# Ffrydiau_core1_1.net
KiCad netlist of a schematic drawn in EAGLE
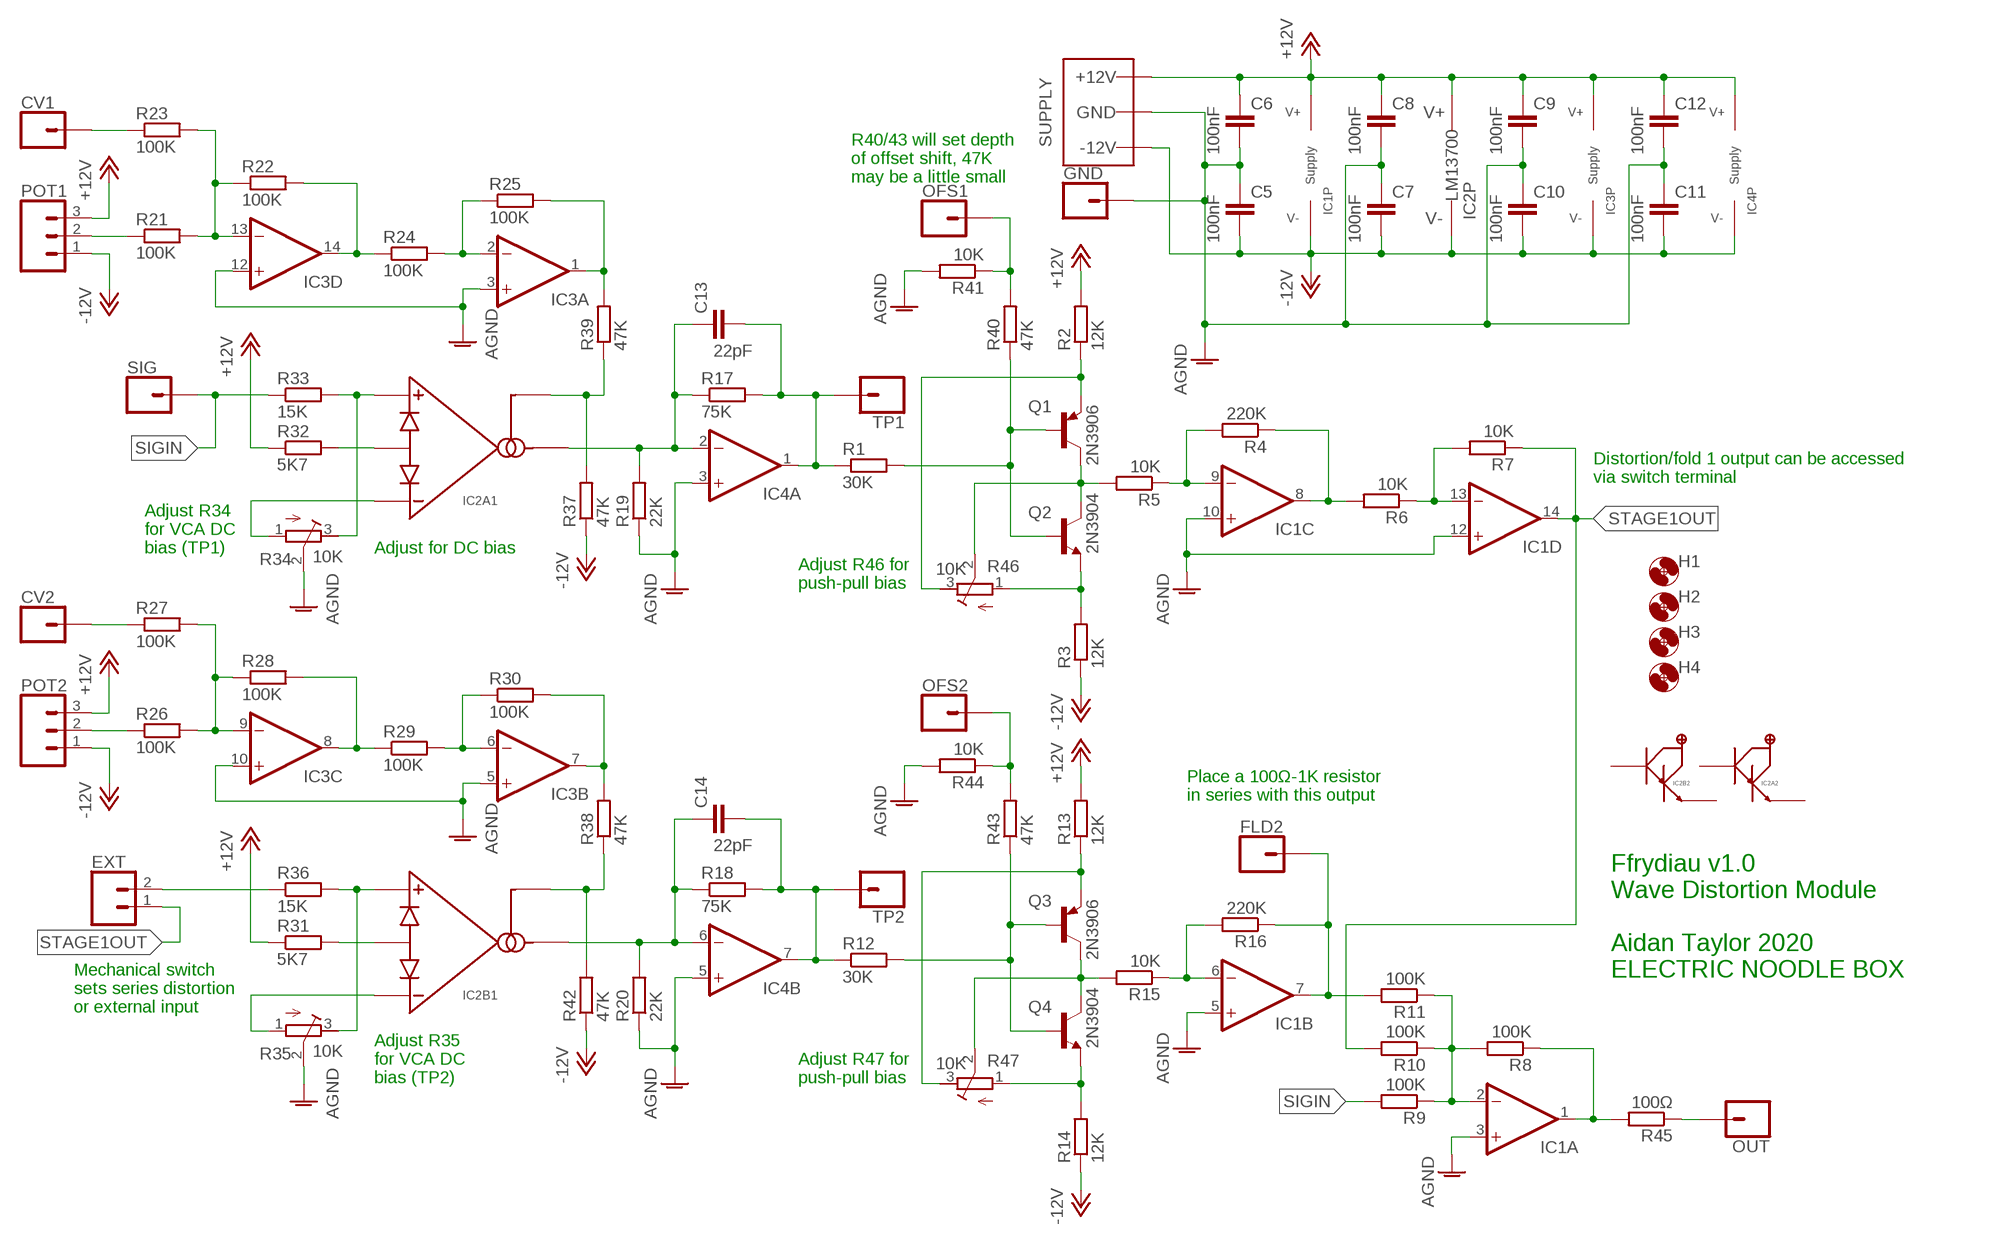
[diagram p0: schematic, sheet 1]

(export (version "E")
  (design (tool "Eeschema 10.0.6"))
  (components
    (comp (ref "C5")
      (value "100nF")
      (footprint "eagle-import:C050-025X075")
      (libsource (lib "eagle-import") (part "C-EU050-025X075"))
    )
    (comp (ref "C6")
      (value "100nF")
      (footprint "eagle-import:C050-025X075")
      (libsource (lib "eagle-import") (part "C-EU050-025X075"))
    )
    (comp (ref "C7")
      (value "100nF")
      (footprint "eagle-import:C050-025X075")
      (libsource (lib "eagle-import") (part "C-EU050-025X075"))
    )
    (comp (ref "C8")
      (value "100nF")
      (footprint "eagle-import:C050-025X075")
      (libsource (lib "eagle-import") (part "C-EU050-025X075"))
    )
    (comp (ref "C9")
      (value "100nF")
      (footprint "eagle-import:C050-025X075")
      (libsource (lib "eagle-import") (part "C-EU050-025X075"))
    )
    (comp (ref "C10")
      (value "100nF")
      (footprint "eagle-import:C050-025X075")
      (libsource (lib "eagle-import") (part "C-EU050-025X075"))
    )
    (comp (ref "C11")
      (value "100nF")
      (footprint "eagle-import:C050-025X075")
      (libsource (lib "eagle-import") (part "C-EU050-025X075"))
    )
    (comp (ref "C12")
      (value "100nF")
      (footprint "eagle-import:C050-025X075")
      (libsource (lib "eagle-import") (part "C-EU050-025X075"))
    )
    (comp (ref "C13")
      (value "22pF")
      (footprint "eagle-import:C050-025X075")
      (libsource (lib "eagle-import") (part "C-EU050-025X075"))
    )
    (comp (ref "C14")
      (value "22pF")
      (footprint "eagle-import:C050-025X075")
      (libsource (lib "eagle-import") (part "C-EU050-025X075"))
    )
    (comp (ref "CV1")
      (value "1XWIREPAD")
      (footprint "eagle-import:1X01")
      (libsource (lib "eagle-import") (part "1XWIREPAD"))
    )
    (comp (ref "CV2")
      (value "1XWIREPAD")
      (footprint "eagle-import:1X01")
      (libsource (lib "eagle-import") (part "1XWIREPAD"))
    )
    (comp (ref "EXT")
      (value "2XWIREPAD")
      (footprint "eagle-import:1X02")
      (libsource (lib "eagle-import") (part "2XWIREPAD"))
    )
    (comp (ref "FLD2")
      (value "1XWIREPAD")
      (footprint "eagle-import:1X01")
      (libsource (lib "eagle-import") (part "1XWIREPAD"))
    )
    (comp (ref "GND")
      (value "1XWIREPAD")
      (footprint "eagle-import:1X01")
      (libsource (lib "eagle-import") (part "1XWIREPAD"))
    )
    (comp (ref "H1")
      (value "MOUNT-HOLE3.2")
      (footprint "eagle-import:3,2")
      (libsource (lib "eagle-import") (part "MOUNT-HOLE3.2"))
    )
    (comp (ref "H2")
      (value "MOUNT-HOLE3.2")
      (footprint "eagle-import:3,2")
      (libsource (lib "eagle-import") (part "MOUNT-HOLE3.2"))
    )
    (comp (ref "H3")
      (value "MOUNT-HOLE3.2")
      (footprint "eagle-import:3,2")
      (libsource (lib "eagle-import") (part "MOUNT-HOLE3.2"))
    )
    (comp (ref "H4")
      (value "MOUNT-HOLE3.2")
      (footprint "eagle-import:3,2")
      (libsource (lib "eagle-import") (part "MOUNT-HOLE3.2"))
    )
    (comp (ref "IC1")
      (value "TL0X4DIL")
      (footprint "eagle-import:DIL14")
      (libsource (lib "eagle-import") (part "TL0X4DIL"))
    )
    (comp (ref "IC2")
      (value "LM13700DIL")
      (footprint "eagle-import:DIL16")
      (libsource (lib "eagle-import") (part "LM13700DIL"))
    )
    (comp (ref "IC3")
      (value "TL0X4DIL")
      (footprint "eagle-import:DIL14")
      (libsource (lib "eagle-import") (part "TL0X4DIL"))
    )
    (comp (ref "IC4")
      (value "TL0X2DIL")
      (footprint "eagle-import:DIL08")
      (libsource (lib "eagle-import") (part "TL0X2DIL"))
    )
    (comp (ref "OFS1")
      (value "1XWIREPAD")
      (footprint "eagle-import:1X01")
      (libsource (lib "eagle-import") (part "1XWIREPAD"))
    )
    (comp (ref "OFS2")
      (value "1XWIREPAD")
      (footprint "eagle-import:1X01")
      (libsource (lib "eagle-import") (part "1XWIREPAD"))
    )
    (comp (ref "OUT")
      (value "1XWIREPAD")
      (footprint "eagle-import:1X01")
      (libsource (lib "eagle-import") (part "1XWIREPAD"))
    )
    (comp (ref "POT1")
      (value "3XWIREPAD")
      (footprint "eagle-import:1X03")
      (libsource (lib "eagle-import") (part "3XWIREPAD"))
    )
    (comp (ref "POT2")
      (value "3XWIREPAD")
      (footprint "eagle-import:1X03")
      (libsource (lib "eagle-import") (part "3XWIREPAD"))
    )
    (comp (ref "Q1")
      (value "2N3906")
      (footprint "eagle-import:TO92")
      (libsource (lib "eagle-import") (part "2N3906"))
    )
    (comp (ref "Q2")
      (value "2N3904")
      (footprint "eagle-import:TO92")
      (libsource (lib "eagle-import") (part "2N3904"))
    )
    (comp (ref "Q3")
      (value "2N3906")
      (footprint "eagle-import:TO92")
      (libsource (lib "eagle-import") (part "2N3906"))
    )
    (comp (ref "Q4")
      (value "2N3904")
      (footprint "eagle-import:TO92")
      (libsource (lib "eagle-import") (part "2N3904"))
    )
    (comp (ref "R1")
      (value "30K")
      (footprint "eagle-import:0207_7")
      (libsource (lib "eagle-import") (part "R-EU_0207/7"))
    )
    (comp (ref "R2")
      (value "12K")
      (footprint "eagle-import:0207_7")
      (libsource (lib "eagle-import") (part "R-EU_0207/7"))
    )
    (comp (ref "R3")
      (value "12K")
      (footprint "eagle-import:0207_7")
      (libsource (lib "eagle-import") (part "R-EU_0207/7"))
    )
    (comp (ref "R4")
      (value "220K")
      (footprint "eagle-import:0207_7")
      (libsource (lib "eagle-import") (part "R-EU_0207/7"))
    )
    (comp (ref "R5")
      (value "10K")
      (footprint "eagle-import:0207_7")
      (libsource (lib "eagle-import") (part "R-EU_0207/7"))
    )
    (comp (ref "R6")
      (value "10K")
      (footprint "eagle-import:0207_7")
      (libsource (lib "eagle-import") (part "R-EU_0207/7"))
    )
    (comp (ref "R7")
      (value "10K")
      (footprint "eagle-import:0207_7")
      (libsource (lib "eagle-import") (part "R-EU_0207/7"))
    )
    (comp (ref "R8")
      (value "100K")
      (footprint "eagle-import:0207_7")
      (libsource (lib "eagle-import") (part "R-EU_0207/7"))
    )
    (comp (ref "R9")
      (value "100K")
      (footprint "eagle-import:0207_7")
      (libsource (lib "eagle-import") (part "R-EU_0207/7"))
    )
    (comp (ref "R10")
      (value "100K")
      (footprint "eagle-import:0207_7")
      (libsource (lib "eagle-import") (part "R-EU_0207/7"))
    )
    (comp (ref "R11")
      (value "100K")
      (footprint "eagle-import:0207_7")
      (libsource (lib "eagle-import") (part "R-EU_0207/7"))
    )
    (comp (ref "R12")
      (value "30K")
      (footprint "eagle-import:0207_7")
      (libsource (lib "eagle-import") (part "R-EU_0207/7"))
    )
    (comp (ref "R13")
      (value "12K")
      (footprint "eagle-import:0207_7")
      (libsource (lib "eagle-import") (part "R-EU_0207/7"))
    )
    (comp (ref "R14")
      (value "12K")
      (footprint "eagle-import:0207_7")
      (libsource (lib "eagle-import") (part "R-EU_0207/7"))
    )
    (comp (ref "R15")
      (value "10K")
      (footprint "eagle-import:0207_7")
      (libsource (lib "eagle-import") (part "R-EU_0207/7"))
    )
    (comp (ref "R16")
      (value "220K")
      (footprint "eagle-import:0207_7")
      (libsource (lib "eagle-import") (part "R-EU_0207/7"))
    )
    (comp (ref "R17")
      (value "75K")
      (footprint "eagle-import:0207_7")
      (libsource (lib "eagle-import") (part "R-EU_0207/7"))
    )
    (comp (ref "R18")
      (value "75K")
      (footprint "eagle-import:0207_7")
      (libsource (lib "eagle-import") (part "R-EU_0207/7"))
    )
    (comp (ref "R19")
      (value "22K")
      (footprint "eagle-import:0207_7")
      (libsource (lib "eagle-import") (part "R-EU_0207/7"))
    )
    (comp (ref "R20")
      (value "22K")
      (footprint "eagle-import:0207_7")
      (libsource (lib "eagle-import") (part "R-EU_0207/7"))
    )
    (comp (ref "R21")
      (value "100K")
      (footprint "eagle-import:0207_7")
      (libsource (lib "eagle-import") (part "R-EU_0207/7"))
    )
    (comp (ref "R22")
      (value "100K")
      (footprint "eagle-import:0207_7")
      (libsource (lib "eagle-import") (part "R-EU_0207/7"))
    )
    (comp (ref "R23")
      (value "100K")
      (footprint "eagle-import:0207_7")
      (libsource (lib "eagle-import") (part "R-EU_0207/7"))
    )
    (comp (ref "R24")
      (value "100K")
      (footprint "eagle-import:0207_7")
      (libsource (lib "eagle-import") (part "R-EU_0207/7"))
    )
    (comp (ref "R25")
      (value "100K")
      (footprint "eagle-import:0207_7")
      (libsource (lib "eagle-import") (part "R-EU_0207/7"))
    )
    (comp (ref "R26")
      (value "100K")
      (footprint "eagle-import:0207_7")
      (libsource (lib "eagle-import") (part "R-EU_0207/7"))
    )
    (comp (ref "R27")
      (value "100K")
      (footprint "eagle-import:0207_7")
      (libsource (lib "eagle-import") (part "R-EU_0207/7"))
    )
    (comp (ref "R28")
      (value "100K")
      (footprint "eagle-import:0207_7")
      (libsource (lib "eagle-import") (part "R-EU_0207/7"))
    )
    (comp (ref "R29")
      (value "100K")
      (footprint "eagle-import:0207_7")
      (libsource (lib "eagle-import") (part "R-EU_0207/7"))
    )
    (comp (ref "R30")
      (value "100K")
      (footprint "eagle-import:0207_7")
      (libsource (lib "eagle-import") (part "R-EU_0207/7"))
    )
    (comp (ref "R31")
      (value "5K7")
      (footprint "eagle-import:0207_7")
      (libsource (lib "eagle-import") (part "R-EU_0207/7"))
    )
    (comp (ref "R32")
      (value "5K7")
      (footprint "eagle-import:0207_7")
      (libsource (lib "eagle-import") (part "R-EU_0207/7"))
    )
    (comp (ref "R33")
      (value "15K")
      (footprint "eagle-import:0207_7")
      (libsource (lib "eagle-import") (part "R-EU_0207/7"))
    )
    (comp (ref "R34")
      (value "10K")
      (footprint "eagle-import:RTRIM3296W")
      (libsource (lib "eagle-import") (part "R-TRIMM3296W"))
    )
    (comp (ref "R35")
      (value "10K")
      (footprint "eagle-import:RTRIM3296W")
      (libsource (lib "eagle-import") (part "R-TRIMM3296W"))
    )
    (comp (ref "R36")
      (value "15K")
      (footprint "eagle-import:0207_7")
      (libsource (lib "eagle-import") (part "R-EU_0207/7"))
    )
    (comp (ref "R37")
      (value "47K")
      (footprint "eagle-import:0207_7")
      (libsource (lib "eagle-import") (part "R-EU_0207/7"))
    )
    (comp (ref "R38")
      (value "47K")
      (footprint "eagle-import:0207_7")
      (libsource (lib "eagle-import") (part "R-EU_0207/7"))
    )
    (comp (ref "R39")
      (value "47K")
      (footprint "eagle-import:0207_7")
      (libsource (lib "eagle-import") (part "R-EU_0207/7"))
    )
    (comp (ref "R40")
      (value "47K")
      (footprint "eagle-import:0207_7")
      (libsource (lib "eagle-import") (part "R-EU_0207/7"))
    )
    (comp (ref "R41")
      (value "10K")
      (footprint "eagle-import:0207_7")
      (libsource (lib "eagle-import") (part "R-EU_0207/7"))
    )
    (comp (ref "R42")
      (value "47K")
      (footprint "eagle-import:0207_7")
      (libsource (lib "eagle-import") (part "R-EU_0207/7"))
    )
    (comp (ref "R43")
      (value "47K")
      (footprint "eagle-import:0207_7")
      (libsource (lib "eagle-import") (part "R-EU_0207/7"))
    )
    (comp (ref "R44")
      (value "10K")
      (footprint "eagle-import:0207_7")
      (libsource (lib "eagle-import") (part "R-EU_0207/7"))
    )
    (comp (ref "R45")
      (value "100Ω")
      (footprint "eagle-import:0207_7")
      (libsource (lib "eagle-import") (part "R-EU_0207/7"))
    )
    (comp (ref "R46")
      (value "10K")
      (footprint "eagle-import:RTRIM3296W")
      (libsource (lib "eagle-import") (part "R-TRIMM3296W"))
    )
    (comp (ref "R47")
      (value "10K")
      (footprint "eagle-import:RTRIM3296W")
      (libsource (lib "eagle-import") (part "R-TRIMM3296W"))
    )
    (comp (ref "SIG")
      (value "1XWIREPAD")
      (footprint "eagle-import:1X01")
      (libsource (lib "eagle-import") (part "1XWIREPAD"))
    )
    (comp (ref "TP1")
      (value "1XWIREPAD")
      (footprint "eagle-import:1X01")
      (libsource (lib "eagle-import") (part "1XWIREPAD"))
    )
    (comp (ref "TP2")
      (value "1XWIREPAD")
      (footprint "eagle-import:1X01")
      (libsource (lib "eagle-import") (part "1XWIREPAD"))
    )
    (comp (ref "WP1")
      (value "COMBO_SUPPLY_HEADER")
      (footprint "eagle-import:COMBINED_POWER")
      (libsource (lib "eagle-import") (part "COMBO_SUPPLY_HEADER"))
    )
  )
  (nets
    (net (code "1") (name "+12V") (class "Default")
      (node (ref "C12") (pin "1") (pinfunction "1_1") (pintype "passive"))
      (node (ref "C6") (pin "1") (pinfunction "1_1") (pintype "passive"))
      (node (ref "C8") (pin "1") (pinfunction "1_1") (pintype "passive"))
      (node (ref "C9") (pin "1") (pinfunction "1_1") (pintype "passive"))
      (node (ref "IC1") (pin "4") (pinfunction "V+_4") (pintype "bidirectional"))
      (node (ref "IC2") (pin "11") (pinfunction "V+_11") (pintype "power_in"))
      (node (ref "IC3") (pin "4") (pinfunction "V+_4") (pintype "bidirectional"))
      (node (ref "IC4") (pin "8") (pinfunction "V+_8") (pintype "bidirectional"))
      (node (ref "POT1") (pin "3") (pinfunction "3_3") (pintype "passive"))
      (node (ref "POT2") (pin "3") (pinfunction "3_3") (pintype "passive"))
      (node (ref "R13") (pin "2") (pinfunction "2_2") (pintype "passive"))
      (node (ref "R2") (pin "2") (pinfunction "2_2") (pintype "passive"))
      (node (ref "R31") (pin "1") (pinfunction "1_1") (pintype "passive"))
      (node (ref "R32") (pin "1") (pinfunction "1_1") (pintype "passive"))
      (node (ref "WP1") (pin "V+1") (pinfunction "V++_V+1") (pintype "power_in"))
      (node (ref "WP1") (pin "V+2") (pinfunction "V++_V+2") (pintype "power_in"))
      (node (ref "WP1") (pin "V+3") (pinfunction "V++_V+3") (pintype "power_in"))
    )
    (net (code "2") (name "-12V") (class "Default")
      (node (ref "C10") (pin "2") (pinfunction "2_2") (pintype "passive"))
      (node (ref "C11") (pin "2") (pinfunction "2_2") (pintype "passive"))
      (node (ref "C5") (pin "2") (pinfunction "2_2") (pintype "passive"))
      (node (ref "C7") (pin "2") (pinfunction "2_2") (pintype "passive"))
      (node (ref "IC1") (pin "11") (pinfunction "V-_11") (pintype "bidirectional"))
      (node (ref "IC2") (pin "6") (pinfunction "V-_6") (pintype "power_in"))
      (node (ref "IC3") (pin "11") (pinfunction "V-_11") (pintype "bidirectional"))
      (node (ref "IC4") (pin "4") (pinfunction "V-_4") (pintype "bidirectional"))
      (node (ref "POT1") (pin "1") (pinfunction "1_1") (pintype "passive"))
      (node (ref "POT2") (pin "1") (pinfunction "1_1") (pintype "passive"))
      (node (ref "R14") (pin "1") (pinfunction "1_1") (pintype "passive"))
      (node (ref "R3") (pin "1") (pinfunction "1_1") (pintype "passive"))
      (node (ref "R37") (pin "1") (pinfunction "1_1") (pintype "passive"))
      (node (ref "R42") (pin "1") (pinfunction "1_1") (pintype "passive"))
      (node (ref "WP1") (pin "V-1") (pinfunction "V--_V-1") (pintype "power_in"))
      (node (ref "WP1") (pin "V-2") (pinfunction "V--_V-2") (pintype "power_in"))
      (node (ref "WP1") (pin "V-3") (pinfunction "V--_V-3") (pintype "power_in"))
    )
    (net (code "3") (name "AGND") (class "Default")
      (node (ref "C10") (pin "1") (pinfunction "1_1") (pintype "passive"))
      (node (ref "C11") (pin "1") (pinfunction "1_1") (pintype "passive"))
      (node (ref "C12") (pin "2") (pinfunction "2_2") (pintype "passive"))
      (node (ref "C5") (pin "1") (pinfunction "1_1") (pintype "passive"))
      (node (ref "C6") (pin "2") (pinfunction "2_2") (pintype "passive"))
      (node (ref "C7") (pin "1") (pinfunction "1_1") (pintype "passive"))
      (node (ref "C8") (pin "2") (pinfunction "2_2") (pintype "passive"))
      (node (ref "C9") (pin "2") (pinfunction "2_2") (pintype "passive"))
      (node (ref "GND") (pin "1") (pinfunction "1_1") (pintype "passive"))
      (node (ref "IC1") (pin "10") (pinfunction "+IN_10") (pintype "input"))
      (node (ref "IC1") (pin "12") (pinfunction "+IN_12") (pintype "input"))
      (node (ref "IC1") (pin "3") (pinfunction "+IN_3") (pintype "input"))
      (node (ref "IC1") (pin "5") (pinfunction "+IN_5") (pintype "input"))
      (node (ref "IC3") (pin "10") (pinfunction "+IN_10") (pintype "input"))
      (node (ref "IC3") (pin "12") (pinfunction "+IN_12") (pintype "input"))
      (node (ref "IC3") (pin "3") (pinfunction "+IN_3") (pintype "input"))
      (node (ref "IC3") (pin "5") (pinfunction "+IN_5") (pintype "input"))
      (node (ref "IC4") (pin "3") (pinfunction "+IN_3") (pintype "input"))
      (node (ref "IC4") (pin "5") (pinfunction "+IN_5") (pintype "input"))
      (node (ref "R19") (pin "1") (pinfunction "1_1") (pintype "passive"))
      (node (ref "R20") (pin "1") (pinfunction "1_1") (pintype "passive"))
      (node (ref "R34") (pin "2") (pinfunction "S_2") (pintype "passive"))
      (node (ref "R35") (pin "2") (pinfunction "S_2") (pintype "passive"))
      (node (ref "R41") (pin "2") (pinfunction "2_2") (pintype "passive"))
      (node (ref "R44") (pin "2") (pinfunction "2_2") (pintype "passive"))
      (node (ref "WP1") (pin "GND1") (pinfunction "AGND_GND1") (pintype "power_in"))
      (node (ref "WP1") (pin "GND2") (pinfunction "AGND_GND2") (pintype "power_in"))
      (node (ref "WP1") (pin "GND3") (pinfunction "AGND_GND3") (pintype "power_in"))
      (node (ref "WP1") (pin "GND4") (pinfunction "AGND_GND4") (pintype "power_in"))
      (node (ref "WP1") (pin "GND5") (pinfunction "AGND_GND5") (pintype "power_in"))
      (node (ref "WP1") (pin "GND6") (pinfunction "AGND_GND6") (pintype "power_in"))
      (node (ref "WP1") (pin "GND7") (pinfunction "AGND_GND7") (pintype "power_in"))
      (node (ref "WP1") (pin "GND8") (pinfunction "AGND_GND8") (pintype "power_in"))
    )
    (net (code "4") (name "Net-(CV1-Pad1)") (class "Default")
      (node (ref "CV1") (pin "1") (pinfunction "1_1") (pintype "passive"))
      (node (ref "R23") (pin "1") (pinfunction "1_1") (pintype "passive"))
    )
    (net (code "5") (name "Net-(CV2-Pad1)") (class "Default")
      (node (ref "CV2") (pin "1") (pinfunction "1_1") (pintype "passive"))
      (node (ref "R27") (pin "1") (pinfunction "1_1") (pintype "passive"))
    )
    (net (code "6") (name "Net-(EXT-Pad2)") (class "Default")
      (node (ref "EXT") (pin "2") (pinfunction "2_2") (pintype "passive"))
      (node (ref "R36") (pin "1") (pinfunction "1_1") (pintype "passive"))
    )
    (net (code "7") (name "Net-(IC1A--IN)") (class "Default")
      (node (ref "IC1") (pin "2") (pinfunction "-IN_2") (pintype "input"))
      (node (ref "R10") (pin "1") (pinfunction "1_1") (pintype "passive"))
      (node (ref "R11") (pin "1") (pinfunction "1_1") (pintype "passive"))
      (node (ref "R8") (pin "2") (pinfunction "2_2") (pintype "passive"))
      (node (ref "R9") (pin "1") (pinfunction "1_1") (pintype "passive"))
    )
    (net (code "8") (name "Net-(IC1A-OUT)") (class "Default")
      (node (ref "IC1") (pin "1") (pinfunction "OUT_1") (pintype "output"))
      (node (ref "R45") (pin "2") (pinfunction "2_2") (pintype "passive"))
      (node (ref "R8") (pin "1") (pinfunction "1_1") (pintype "passive"))
    )
    (net (code "9") (name "Net-(IC1B--IN)") (class "Default")
      (node (ref "IC1") (pin "6") (pinfunction "-IN_6") (pintype "input"))
      (node (ref "R15") (pin "1") (pinfunction "1_1") (pintype "passive"))
      (node (ref "R16") (pin "2") (pinfunction "2_2") (pintype "passive"))
    )
    (net (code "10") (name "Net-(IC1B-OUT)") (class "Default")
      (node (ref "FLD2") (pin "1") (pinfunction "1_1") (pintype "passive"))
      (node (ref "IC1") (pin "7") (pinfunction "OUT_7") (pintype "output"))
      (node (ref "R11") (pin "2") (pinfunction "2_2") (pintype "passive"))
      (node (ref "R16") (pin "1") (pinfunction "1_1") (pintype "passive"))
    )
    (net (code "11") (name "Net-(IC1C--IN)") (class "Default")
      (node (ref "IC1") (pin "9") (pinfunction "-IN_9") (pintype "input"))
      (node (ref "R4") (pin "2") (pinfunction "2_2") (pintype "passive"))
      (node (ref "R5") (pin "1") (pinfunction "1_1") (pintype "passive"))
    )
    (net (code "12") (name "Net-(IC1C-OUT)") (class "Default")
      (node (ref "IC1") (pin "8") (pinfunction "OUT_8") (pintype "output"))
      (node (ref "R4") (pin "1") (pinfunction "1_1") (pintype "passive"))
      (node (ref "R6") (pin "2") (pinfunction "2_2") (pintype "passive"))
    )
    (net (code "13") (name "Net-(IC1D--IN)") (class "Default")
      (node (ref "IC1") (pin "13") (pinfunction "-IN_13") (pintype "input"))
      (node (ref "R6") (pin "1") (pinfunction "1_1") (pintype "passive"))
      (node (ref "R7") (pin "2") (pinfunction "2_2") (pintype "passive"))
    )
    (net (code "14") (name "Net-(IC2A-AMP+)") (class "Default")
      (node (ref "IC2") (pin "3") (pinfunction "AMP+_3") (pintype "input"))
      (node (ref "R33") (pin "2") (pinfunction "2_2") (pintype "passive"))
      (node (ref "R34") (pin "3") (pinfunction "E_3") (pintype "passive"))
    )
    (net (code "15") (name "Net-(IC2A-AMP-)") (class "Default")
      (node (ref "IC2") (pin "4") (pinfunction "AMP-_4") (pintype "input"))
      (node (ref "R34") (pin "1") (pinfunction "A_1") (pintype "passive"))
    )
    (net (code "16") (name "Net-(IC2A-AMPBIAS)") (class "Default")
      (node (ref "IC2") (pin "1") (pinfunction "AMPBIAS_1") (pintype "input"))
      (node (ref "R37") (pin "2") (pinfunction "2_2") (pintype "passive"))
      (node (ref "R39") (pin "1") (pinfunction "1_1") (pintype "passive"))
    )
    (net (code "17") (name "Net-(IC2A-AMPOUT)") (class "Default")
      (node (ref "C13") (pin "1") (pinfunction "1_1") (pintype "passive"))
      (node (ref "IC2") (pin "5") (pinfunction "AMPOUT_5") (pintype "output"))
      (node (ref "IC4") (pin "2") (pinfunction "-IN_2") (pintype "input"))
      (node (ref "R17") (pin "1") (pinfunction "1_1") (pintype "passive"))
      (node (ref "R19") (pin "2") (pinfunction "2_2") (pintype "passive"))
    )
    (net (code "18") (name "Net-(IC2A-DIODES)") (class "Default")
      (node (ref "IC2") (pin "2") (pinfunction "DIODES_2") (pintype "input"))
      (node (ref "R32") (pin "2") (pinfunction "2_2") (pintype "passive"))
    )
    (net (code "19") (name "Net-(IC2C-AMP+)") (class "Default")
      (node (ref "IC2") (pin "14") (pinfunction "AMP+_14") (pintype "input"))
      (node (ref "R35") (pin "3") (pinfunction "E_3") (pintype "passive"))
      (node (ref "R36") (pin "2") (pinfunction "2_2") (pintype "passive"))
    )
    (net (code "20") (name "Net-(IC2C-AMP-)") (class "Default")
      (node (ref "IC2") (pin "13") (pinfunction "AMP-_13") (pintype "input"))
      (node (ref "R35") (pin "1") (pinfunction "A_1") (pintype "passive"))
    )
    (net (code "21") (name "Net-(IC2C-AMPBIAS)") (class "Default")
      (node (ref "IC2") (pin "16") (pinfunction "AMPBIAS_16") (pintype "input"))
      (node (ref "R38") (pin "1") (pinfunction "1_1") (pintype "passive"))
      (node (ref "R42") (pin "2") (pinfunction "2_2") (pintype "passive"))
    )
    (net (code "22") (name "Net-(IC2C-AMPOUT)") (class "Default")
      (node (ref "C14") (pin "1") (pinfunction "1_1") (pintype "passive"))
      (node (ref "IC2") (pin "12") (pinfunction "AMPOUT_12") (pintype "output"))
      (node (ref "IC4") (pin "6") (pinfunction "-IN_6") (pintype "input"))
      (node (ref "R18") (pin "1") (pinfunction "1_1") (pintype "passive"))
      (node (ref "R20") (pin "2") (pinfunction "2_2") (pintype "passive"))
    )
    (net (code "23") (name "Net-(IC2C-DIODES)") (class "Default")
      (node (ref "IC2") (pin "15") (pinfunction "DIODES_15") (pintype "input"))
      (node (ref "R31") (pin "2") (pinfunction "2_2") (pintype "passive"))
    )
    (net (code "24") (name "Net-(IC3A--IN)") (class "Default")
      (node (ref "IC3") (pin "2") (pinfunction "-IN_2") (pintype "input"))
      (node (ref "R24") (pin "2") (pinfunction "2_2") (pintype "passive"))
      (node (ref "R25") (pin "1") (pinfunction "1_1") (pintype "passive"))
    )
    (net (code "25") (name "Net-(IC3A-OUT)") (class "Default")
      (node (ref "IC3") (pin "1") (pinfunction "OUT_1") (pintype "output"))
      (node (ref "R25") (pin "2") (pinfunction "2_2") (pintype "passive"))
      (node (ref "R39") (pin "2") (pinfunction "2_2") (pintype "passive"))
    )
    (net (code "26") (name "Net-(IC3B--IN)") (class "Default")
      (node (ref "IC3") (pin "6") (pinfunction "-IN_6") (pintype "input"))
      (node (ref "R29") (pin "2") (pinfunction "2_2") (pintype "passive"))
      (node (ref "R30") (pin "1") (pinfunction "1_1") (pintype "passive"))
    )
    (net (code "27") (name "Net-(IC3B-OUT)") (class "Default")
      (node (ref "IC3") (pin "7") (pinfunction "OUT_7") (pintype "output"))
      (node (ref "R30") (pin "2") (pinfunction "2_2") (pintype "passive"))
      (node (ref "R38") (pin "2") (pinfunction "2_2") (pintype "passive"))
    )
    (net (code "28") (name "Net-(IC3C--IN)") (class "Default")
      (node (ref "IC3") (pin "9") (pinfunction "-IN_9") (pintype "input"))
      (node (ref "R26") (pin "2") (pinfunction "2_2") (pintype "passive"))
      (node (ref "R27") (pin "2") (pinfunction "2_2") (pintype "passive"))
      (node (ref "R28") (pin "1") (pinfunction "1_1") (pintype "passive"))
    )
    (net (code "29") (name "Net-(IC3C-OUT)") (class "Default")
      (node (ref "IC3") (pin "8") (pinfunction "OUT_8") (pintype "output"))
      (node (ref "R28") (pin "2") (pinfunction "2_2") (pintype "passive"))
      (node (ref "R29") (pin "1") (pinfunction "1_1") (pintype "passive"))
    )
    (net (code "30") (name "Net-(IC3D--IN)") (class "Default")
      (node (ref "IC3") (pin "13") (pinfunction "-IN_13") (pintype "input"))
      (node (ref "R21") (pin "2") (pinfunction "2_2") (pintype "passive"))
      (node (ref "R22") (pin "1") (pinfunction "1_1") (pintype "passive"))
      (node (ref "R23") (pin "2") (pinfunction "2_2") (pintype "passive"))
    )
    (net (code "31") (name "Net-(IC3D-OUT)") (class "Default")
      (node (ref "IC3") (pin "14") (pinfunction "OUT_14") (pintype "output"))
      (node (ref "R22") (pin "2") (pinfunction "2_2") (pintype "passive"))
      (node (ref "R24") (pin "1") (pinfunction "1_1") (pintype "passive"))
    )
    (net (code "32") (name "Net-(IC4A-OUT)") (class "Default")
      (node (ref "C13") (pin "2") (pinfunction "2_2") (pintype "passive"))
      (node (ref "IC4") (pin "1") (pinfunction "OUT_1") (pintype "output"))
      (node (ref "R1") (pin "1") (pinfunction "1_1") (pintype "passive"))
      (node (ref "R17") (pin "2") (pinfunction "2_2") (pintype "passive"))
      (node (ref "TP1") (pin "1") (pinfunction "1_1") (pintype "passive"))
    )
    (net (code "33") (name "Net-(IC4B-OUT)") (class "Default")
      (node (ref "C14") (pin "2") (pinfunction "2_2") (pintype "passive"))
      (node (ref "IC4") (pin "7") (pinfunction "OUT_7") (pintype "output"))
      (node (ref "R12") (pin "1") (pinfunction "1_1") (pintype "passive"))
      (node (ref "R18") (pin "2") (pinfunction "2_2") (pintype "passive"))
      (node (ref "TP2") (pin "1") (pinfunction "1_1") (pintype "passive"))
    )
    (net (code "34") (name "Net-(OFS1-Pad1)") (class "Default")
      (node (ref "OFS1") (pin "1") (pinfunction "1_1") (pintype "passive"))
      (node (ref "R40") (pin "2") (pinfunction "2_2") (pintype "passive"))
      (node (ref "R41") (pin "1") (pinfunction "1_1") (pintype "passive"))
    )
    (net (code "35") (name "Net-(OFS2-Pad1)") (class "Default")
      (node (ref "OFS2") (pin "1") (pinfunction "1_1") (pintype "passive"))
      (node (ref "R43") (pin "2") (pinfunction "2_2") (pintype "passive"))
      (node (ref "R44") (pin "1") (pinfunction "1_1") (pintype "passive"))
    )
    (net (code "36") (name "Net-(OUT-Pad1)") (class "Default")
      (node (ref "OUT") (pin "1") (pinfunction "1_1") (pintype "passive"))
      (node (ref "R45") (pin "1") (pinfunction "1_1") (pintype "passive"))
    )
    (net (code "37") (name "Net-(POT1-Pad2)") (class "Default")
      (node (ref "POT1") (pin "2") (pinfunction "2_2") (pintype "passive"))
      (node (ref "R21") (pin "1") (pinfunction "1_1") (pintype "passive"))
    )
    (net (code "38") (name "Net-(POT2-Pad2)") (class "Default")
      (node (ref "POT2") (pin "2") (pinfunction "2_2") (pintype "passive"))
      (node (ref "R26") (pin "1") (pinfunction "1_1") (pintype "passive"))
    )
    (net (code "39") (name "Net-(Q1-B)") (class "Default")
      (node (ref "Q1") (pin "2") (pinfunction "B_2") (pintype "passive"))
      (node (ref "Q2") (pin "2") (pinfunction "B_2") (pintype "passive"))
      (node (ref "R1") (pin "2") (pinfunction "2_2") (pintype "passive"))
      (node (ref "R40") (pin "1") (pinfunction "1_1") (pintype "passive"))
    )
    (net (code "40") (name "Net-(Q1-C)") (class "Default")
      (node (ref "Q1") (pin "1") (pinfunction "C_1") (pintype "passive"))
      (node (ref "Q2") (pin "1") (pinfunction "C_1") (pintype "passive"))
      (node (ref "R46") (pin "2") (pinfunction "S_2") (pintype "passive"))
      (node (ref "R5") (pin "2") (pinfunction "2_2") (pintype "passive"))
    )
    (net (code "41") (name "Net-(Q1-E)") (class "Default")
      (node (ref "Q1") (pin "3") (pinfunction "E_3") (pintype "passive"))
      (node (ref "R2") (pin "1") (pinfunction "1_1") (pintype "passive"))
      (node (ref "R46") (pin "3") (pinfunction "E_3") (pintype "passive"))
    )
    (net (code "42") (name "Net-(Q2-E)") (class "Default")
      (node (ref "Q2") (pin "3") (pinfunction "E_3") (pintype "passive"))
      (node (ref "R3") (pin "2") (pinfunction "2_2") (pintype "passive"))
      (node (ref "R46") (pin "1") (pinfunction "A_1") (pintype "passive"))
    )
    (net (code "43") (name "Net-(Q3-B)") (class "Default")
      (node (ref "Q3") (pin "2") (pinfunction "B_2") (pintype "passive"))
      (node (ref "Q4") (pin "2") (pinfunction "B_2") (pintype "passive"))
      (node (ref "R12") (pin "2") (pinfunction "2_2") (pintype "passive"))
      (node (ref "R43") (pin "1") (pinfunction "1_1") (pintype "passive"))
    )
    (net (code "44") (name "Net-(Q3-C)") (class "Default")
      (node (ref "Q3") (pin "1") (pinfunction "C_1") (pintype "passive"))
      (node (ref "Q4") (pin "1") (pinfunction "C_1") (pintype "passive"))
      (node (ref "R15") (pin "2") (pinfunction "2_2") (pintype "passive"))
      (node (ref "R47") (pin "2") (pinfunction "S_2") (pintype "passive"))
    )
    (net (code "45") (name "Net-(Q3-E)") (class "Default")
      (node (ref "Q3") (pin "3") (pinfunction "E_3") (pintype "passive"))
      (node (ref "R13") (pin "1") (pinfunction "1_1") (pintype "passive"))
      (node (ref "R47") (pin "3") (pinfunction "E_3") (pintype "passive"))
    )
    (net (code "46") (name "Net-(Q4-E)") (class "Default")
      (node (ref "Q4") (pin "3") (pinfunction "E_3") (pintype "passive"))
      (node (ref "R14") (pin "2") (pinfunction "2_2") (pintype "passive"))
      (node (ref "R47") (pin "1") (pinfunction "A_1") (pintype "passive"))
    )
    (net (code "47") (name "SIGIN") (class "Default")
      (node (ref "R33") (pin "1") (pinfunction "1_1") (pintype "passive"))
      (node (ref "R9") (pin "2") (pinfunction "2_2") (pintype "passive"))
      (node (ref "SIG") (pin "1") (pinfunction "1_1") (pintype "passive"))
    )
    (net (code "48") (name "STAGE1OUT") (class "Default")
      (node (ref "EXT") (pin "1") (pinfunction "1_1") (pintype "passive"))
      (node (ref "IC1") (pin "14") (pinfunction "OUT_14") (pintype "output"))
      (node (ref "R10") (pin "2") (pinfunction "2_2") (pintype "passive"))
      (node (ref "R7") (pin "1") (pinfunction "1_1") (pintype "passive"))
    )
    (net (code "49") (name "unconnected-(IC2B-BUFF_IN-Pad7)") (class "Default")
      (node (ref "IC2") (pin "7") (pinfunction "BUFF_IN_7") (pintype "input"))
    )
    (net (code "50") (name "unconnected-(IC2B-BUFF_OUT-Pad8)") (class "Default")
      (node (ref "IC2") (pin "8") (pinfunction "BUFF_OUT_8") (pintype "bidirectional"))
    )
    (net (code "51") (name "unconnected-(IC2D-BUFF_IN-Pad10)") (class "Default")
      (node (ref "IC2") (pin "10") (pinfunction "BUFF_IN_10") (pintype "input"))
    )
    (net (code "52") (name "unconnected-(IC2D-BUFF_OUT-Pad9)") (class "Default")
      (node (ref "IC2") (pin "9") (pinfunction "BUFF_OUT_9") (pintype "bidirectional"))
    )
  )
)
